# Lab2_Scheme.net
KiCad netlist of a schematic drawn in Altium Designer
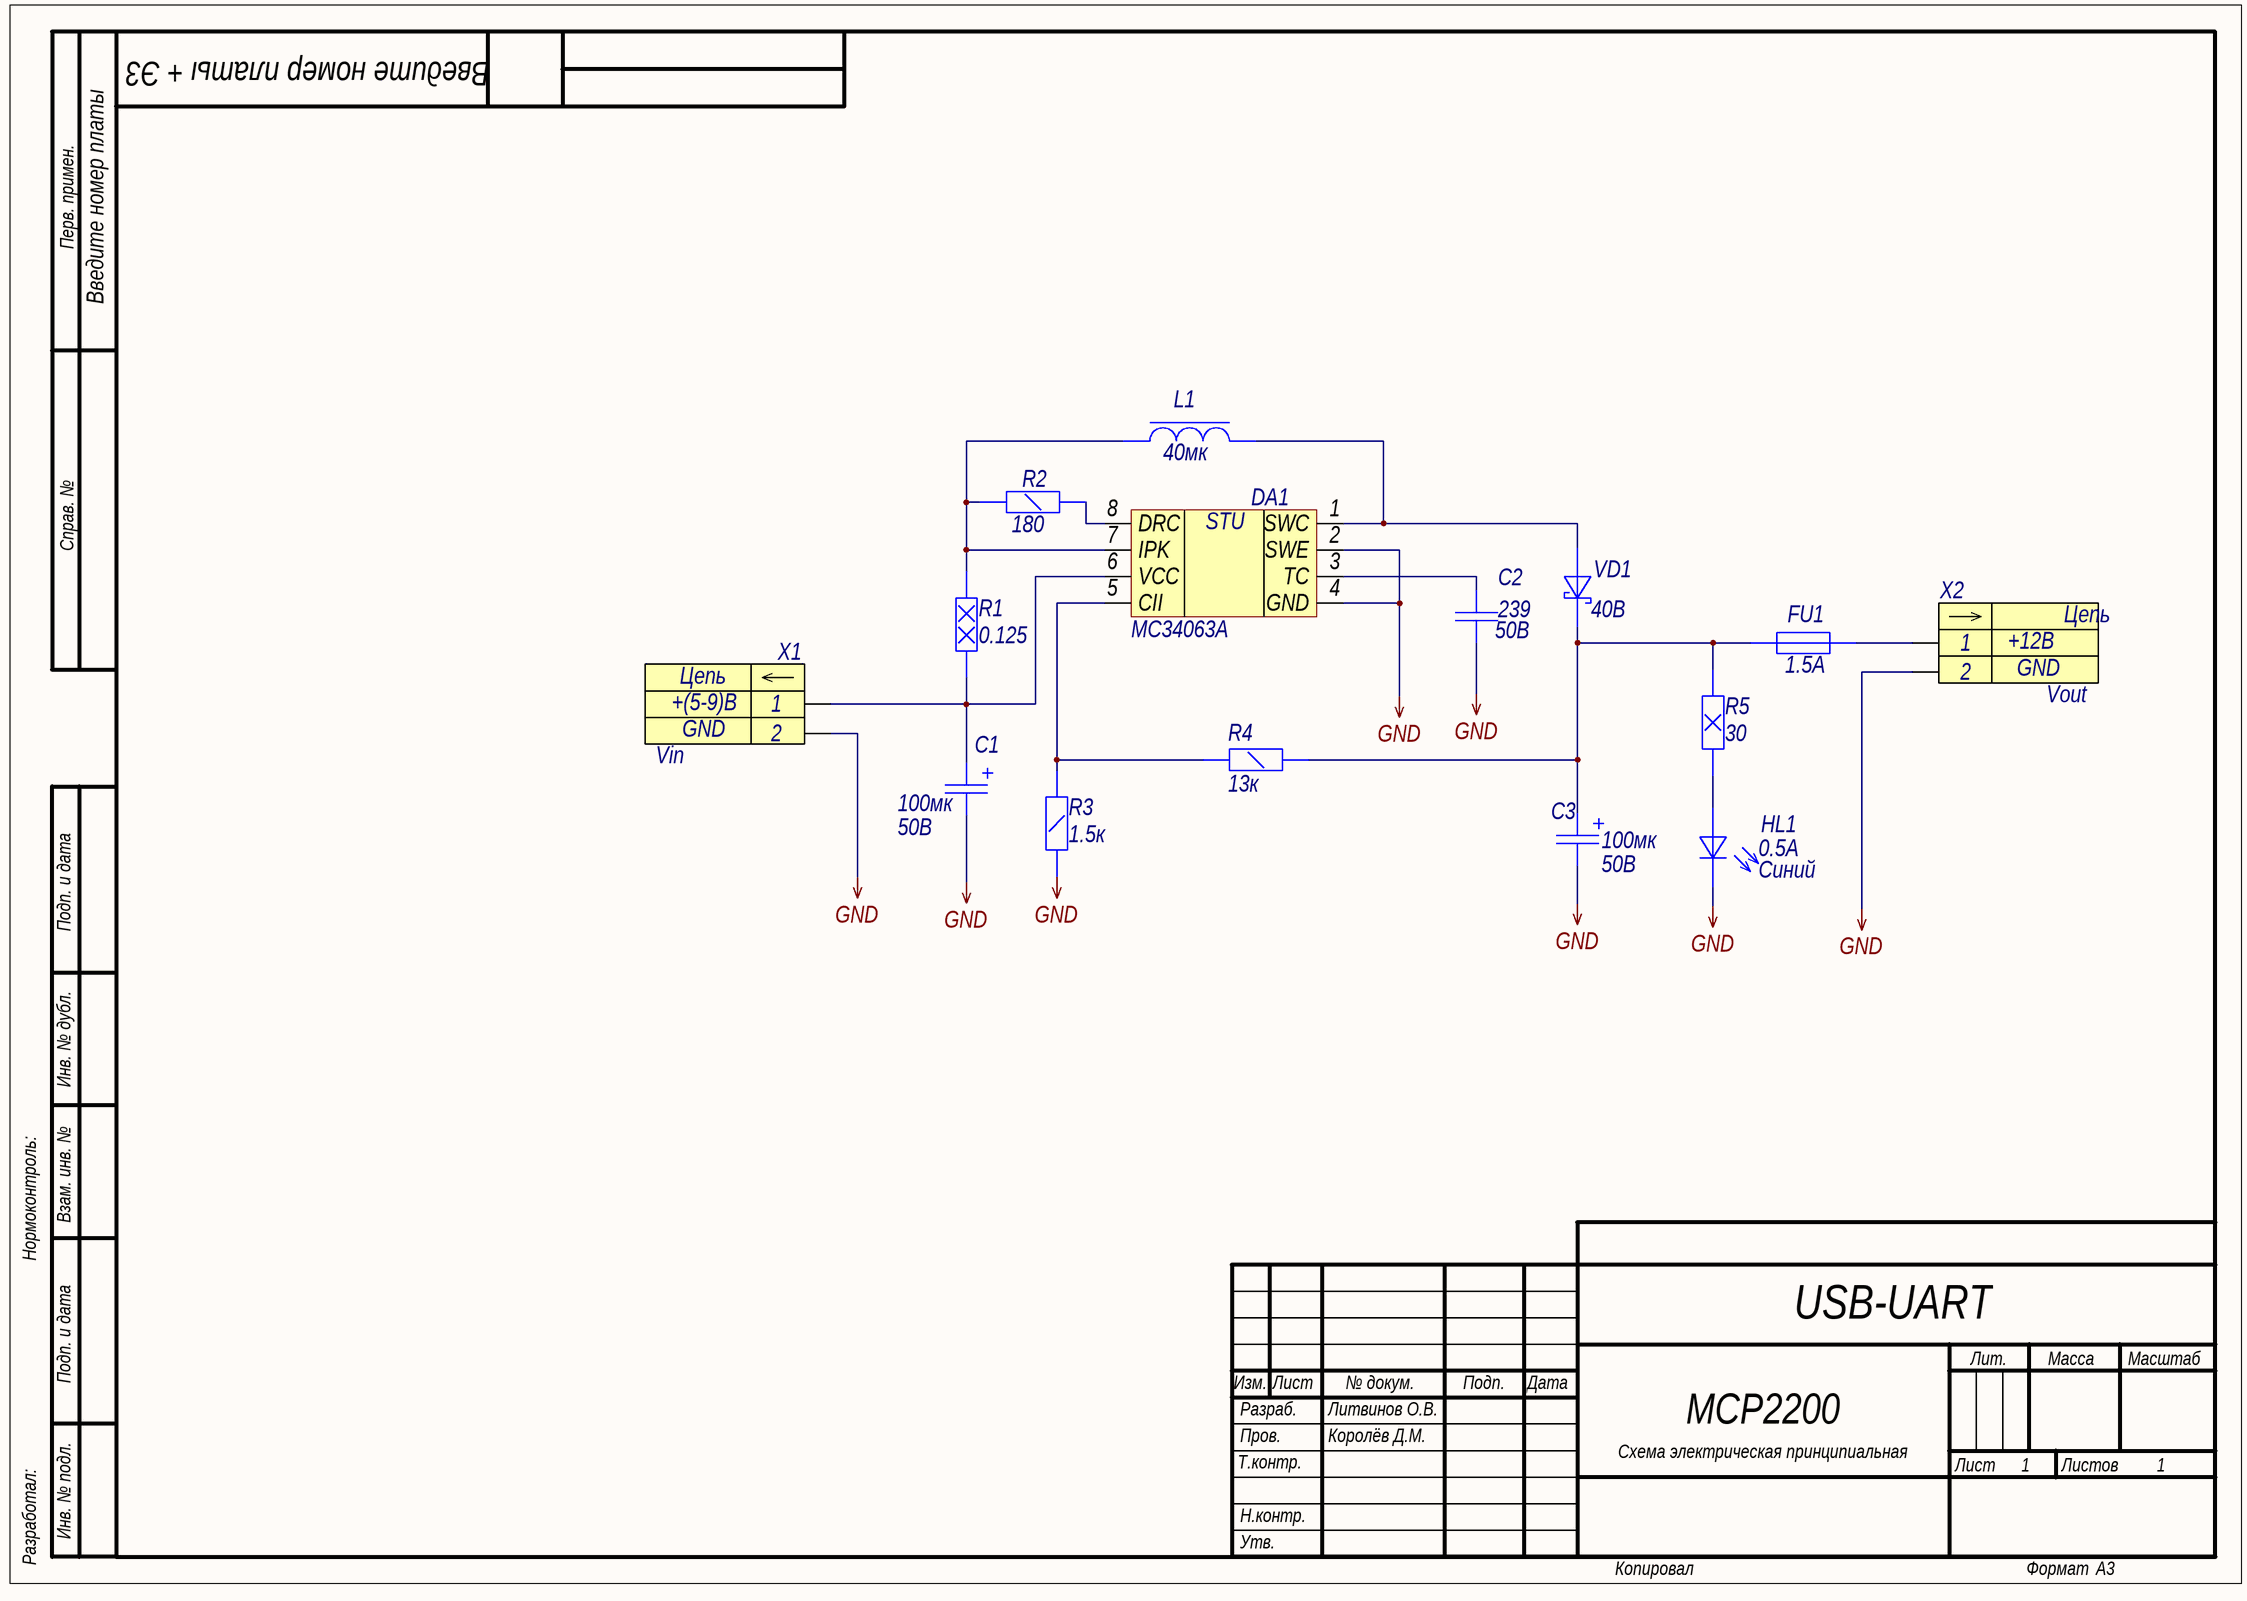
[diagram p0: Lab2_Scheme.SchDoc]

(export (version "E")
  (design (tool "Eeschema 10.0.6"))
  (components
    (comp (ref "C1")
      (value "Capacitor-E")
      (fields
        (field (name "ЁМКОСТЬ") "100мк")
        (field (name "НАПРЯЖЕНИЕ") "50В")
        (field (name "PUBLISHER") "Олег Литвинов")
      )
      (libsource (lib "Capacitor GOST") (part "Capacitor-E"))
    )
    (comp (ref "C2")
      (value "Capacitor")
      (fields
        (field (name "ЁМКОСТЬ") "239")
        (field (name "НАПРЯЖЕНИЕ") "50В")
        (field (name "PUBLISHER") "Andrew Danich")
      )
      (libsource (lib "Capacitor GOST") (part "Capacitor"))
    )
    (comp (ref "C3")
      (value "Capacitor-E")
      (footprint "C1206")
      (fields
        (field (name "ЁМКОСТЬ") "100мк")
        (field (name "НАПРЯЖЕНИЕ") "50В")
        (field (name "PUBLISHER") "Олег Литвинов")
      )
      (libsource (lib "Capacitor GOST") (part "Capacitor-E"))
    )
    (comp (ref "DA1")
      (value "MC34063A")
      (footprint "PCBComponent_1")
      (libsource (lib "MCP2200_UART_USB") (part "MC34063A"))
    )
    (comp (ref "FU1")
      (value "1.5A")
      (footprint "F1812")
      (fields (field (name "Comment") "Fuse"))
      (libsource (lib "Fuse_GOST") (part "Fuse"))
    )
    (comp (ref "HL1")
      (value "LED_3V")
      (footprint "LD0805")
      (fields
        (field (name "ПРЯМОЙ ТОК") "0.5А")
        (field (name "ЦВЕТ") "Синий")
        (field (name "PUBLISHER") "Andrew Danich")
      )
      (libsource (lib "Led GOST") (part "Led-1"))
    )
    (comp (ref "L1")
      (value "40мк")
      (footprint "КИВ-18")
      (fields
        (field (name "PART NUMBER") "КИВ18-100")
        (field (name "TOLERANCE") "±10%")
        (field (name "MANUFACTURER") "ОАО \"МСТАТОР\"")
        (field (name "PUBLISHER") "Andrew Danich")
      )
      (libsource (lib "Lib_GOST") (part "Coil"))
    )
    (comp (ref "R1")
      (value "Resistor_20,0W")
      (footprint "R0805")
      (fields (field (name "СОПРОТИВЛЕНИЕ") "0.125"))
      (libsource (lib "Resistor_GOST") (part "Resistor_20,0W"))
    )
    (comp (ref "R2")
      (value "Resistor_0,25W")
      (footprint "R0805")
      (fields (field (name "СОПРОТИВЛЕНИЕ") "180"))
      (libsource (lib "Resistor_GOST") (part "Resistor_0,25W"))
    )
    (comp (ref "R3")
      (value "1.5к")
      (footprint "R0805")
      (fields (field (name "Comment") "Resistor_0,25W"))
      (libsource (lib "Resistor_GOST") (part "Resistor_0,25W"))
    )
    (comp (ref "R4")
      (value "13к")
      (fields (field (name "Comment") "Resistor_0,25W"))
      (libsource (lib "Resistor_GOST") (part "Resistor_0,25W"))
    )
    (comp (ref "R5")
      (value "Resistor_10,0W")
      (footprint "R0805")
      (fields (field (name "СОПРОТИВЛЕНИЕ") "30"))
      (libsource (lib "Resistor_GOST") (part "Resistor_10,0W"))
    )
    (comp (ref "VD1")
      (value "Schottky")
      (footprint "DO-214AC")
      (description "BYV10-40")
      (fields (field (name "МАКСИМАЛЬНОЕ ОБРАТНОЕ НАПРЯЖЕНИЕ") "40В"))
      (libsource (lib "Diode_GOST") (part "Schottky"))
    )
    (comp (ref "X1")
      (value "Vin")
      (footprint "WF-2")
      (fields (field (name "U") "+(5-9)В") (field (name "GND") "GND") (field (name "CREATE") "DeathSpeaker"))
      (libsource (lib "MCP2200_UART_USB") (part "Vin"))
    )
    (comp (ref "X2")
      (value "Vout")
      (footprint "CWF-2")
      (fields (field (name "U") "+12В") (field (name "GND") "GND") (field (name "CREATE") "DeathSpeaker"))
      (libsource (lib "MCP2200_UART_USB") (part "Vout"))
    )
  )
  (nets
    (net (code "1") (name "GND") (class "Default")
      (node (ref "C1") (pin "2") (pinfunction "2_2") (pintype "passive"))
      (node (ref "C2") (pin "1") (pinfunction "1_1") (pintype "passive"))
      (node (ref "C3") (pin "2") (pinfunction "2_2") (pintype "passive"))
      (node (ref "DA1") (pin "2") (pinfunction "SWE_2") (pintype "passive"))
      (node (ref "DA1") (pin "4") (pinfunction "GND_4") (pintype "passive"))
      (node (ref "HL1") (pin "2") (pinfunction "К_2") (pintype "passive"))
      (node (ref "R3") (pin "1") (pinfunction "1_1") (pintype "passive"))
      (node (ref "X1") (pin "2") (pinfunction "2_2") (pintype "passive"))
      (node (ref "X2") (pin "2") (pinfunction "2_2") (pintype "passive"))
    )
    (net (code "2") (name "Net-(DA1-CII)") (class "Default")
      (node (ref "DA1") (pin "5") (pinfunction "CII_5") (pintype "passive"))
      (node (ref "R3") (pin "2") (pinfunction "2_2") (pintype "passive"))
      (node (ref "R4") (pin "1") (pinfunction "1_1") (pintype "passive"))
    )
    (net (code "3") (name "Net-(DA1-DRC)") (class "Default")
      (node (ref "DA1") (pin "8") (pinfunction "DRC_8") (pintype "passive"))
      (node (ref "R2") (pin "2") (pinfunction "2_2") (pintype "passive"))
    )
    (net (code "4") (name "Net-(DA1-IPK)") (class "Default")
      (node (ref "DA1") (pin "7") (pinfunction "IPK_7") (pintype "passive"))
      (node (ref "L1") (pin "1") (pinfunction "1_1") (pintype "passive"))
      (node (ref "R1") (pin "2") (pinfunction "2_2") (pintype "passive"))
      (node (ref "R2") (pin "1") (pinfunction "1_1") (pintype "passive"))
    )
    (net (code "5") (name "Net-(DA1-SWC)") (class "Default")
      (node (ref "DA1") (pin "1") (pinfunction "SWC_1") (pintype "passive"))
      (node (ref "L1") (pin "2") (pinfunction "2_2") (pintype "passive"))
      (node (ref "VD1") (pin "1") (pinfunction "А_1") (pintype "passive"))
    )
    (net (code "6") (name "Net-(DA1-TC)") (class "Default")
      (node (ref "C2") (pin "2") (pinfunction "2_2") (pintype "passive"))
      (node (ref "DA1") (pin "3") (pinfunction "TC_3") (pintype "passive"))
    )
    (net (code "7") (name "Net-(DA1-VCC)") (class "Default")
      (node (ref "C1") (pin "1") (pinfunction "1_1") (pintype "passive"))
      (node (ref "DA1") (pin "6") (pinfunction "VCC_6") (pintype "passive"))
      (node (ref "R1") (pin "1") (pinfunction "1_1") (pintype "passive"))
      (node (ref "X1") (pin "1") (pinfunction "1_1") (pintype "passive"))
    )
    (net (code "8") (name "Net-(FU1-Pad1)") (class "Default")
      (node (ref "FU1") (pin "1") (pinfunction "1_1") (pintype "passive"))
      (node (ref "X2") (pin "1") (pinfunction "1_1") (pintype "passive"))
    )
    (net (code "9") (name "Net-(HL1-А)") (class "Default")
      (node (ref "HL1") (pin "1") (pinfunction "А_1") (pintype "passive"))
      (node (ref "R5") (pin "1") (pinfunction "1_1") (pintype "passive"))
    )
    (net (code "10") (name "Net-(VD1-К)") (class "Default")
      (node (ref "C3") (pin "1") (pinfunction "1_1") (pintype "passive"))
      (node (ref "FU1") (pin "2") (pinfunction "2_2") (pintype "passive"))
      (node (ref "R4") (pin "2") (pinfunction "2_2") (pintype "passive"))
      (node (ref "R5") (pin "2") (pinfunction "2_2") (pintype "passive"))
      (node (ref "VD1") (pin "2") (pinfunction "К_2") (pintype "passive"))
    )
  )
)
